# 10-USB-Prog.net
KiCad netlist of a schematic drawn in Altium Designer
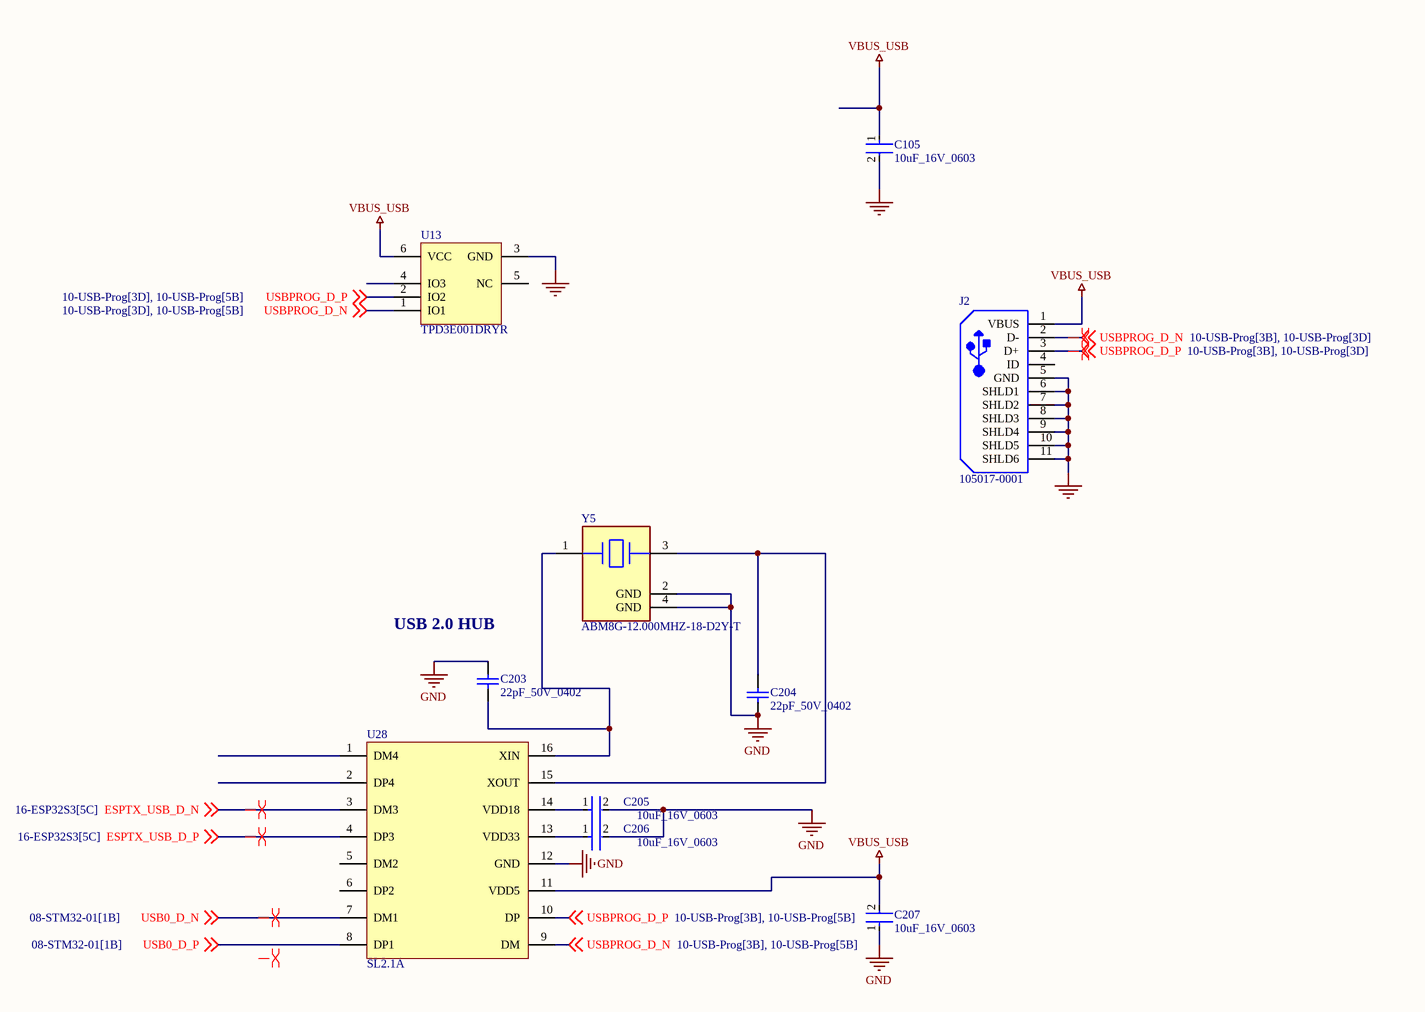
[diagram p0: 10-USB-Prog.SchDoc]

(export (version "E")
  (design (tool "Eeschema 10.0.6"))
  (components
    (comp (ref "C105")
      (value "10uF_16V_0603")
      (footprint "FP-0603-L_1_6_0_2-W_0_8_0-MFG")
      (description "Multilayer Ceramic Capacitor 10uF 16V X5R 20% SMD 0603 T/R")
      (fields (field (name "TOLERANCE") "20%"))
      (libsource (lib "Altium Content Vault") (part "b4654b650e69147ec39a6b967a45e02"))
    )
    (comp (ref "C203")
      (value "22pF_50V_0402")
      (footprint "CAPC1005X55X25ML05T05")
      (description "Chip Capacitor, 22 pF, +/- 5%, 50 V, -55 to 125 degC, 0402 (1005 Metric), RoHS, Tape and Reel")
      (fields (field (name "MANUFACTURER") "Yageo") (field (name "TOLERANCE") "5%"))
      (libsource (lib "Altium Content Vault") (part "CAP-NP-2"))
    )
    (comp (ref "C204")
      (value "22pF_50V_0402")
      (footprint "CAPC1005X55X25ML05T05")
      (description "Chip Capacitor, 22 pF, +/- 5%, 50 V, -55 to 125 degC, 0402 (1005 Metric), RoHS, Tape and Reel")
      (fields (field (name "MANUFACTURER") "Yageo") (field (name "TOLERANCE") "5%"))
      (libsource (lib "Altium Content Vault") (part "CAP-NP-2"))
    )
    (comp (ref "C205")
      (value "10uF_16V_0603")
      (footprint "FP-0603-L_1_6_0_2-W_0_8_0-MFG")
      (description "Multilayer Ceramic Capacitor 10uF 16V X5R 20% SMD 0603 T/R")
      (fields (field (name "TOLERANCE") "20%"))
      (libsource (lib "Altium Content Vault") (part "b4654b650e69147ec39a6b967a45e02"))
    )
    (comp (ref "C206")
      (value "10uF_16V_0603")
      (footprint "FP-0603-L_1_6_0_2-W_0_8_0-MFG")
      (description "Multilayer Ceramic Capacitor 10uF 16V X5R 20% SMD 0603 T/R")
      (fields (field (name "TOLERANCE") "20%"))
      (libsource (lib "Altium Content Vault") (part "b4654b650e69147ec39a6b967a45e02"))
    )
    (comp (ref "C207")
      (value "10uF_16V_0603")
      (footprint "FP-0603-L_1_6_0_2-W_0_8_0-MFG")
      (description "Multilayer Ceramic Capacitor 10uF 16V X5R 20% SMD 0603 T/R")
      (fields (field (name "TOLERANCE") "20%"))
      (libsource (lib "Altium Content Vault") (part "b4654b650e69147ec39a6b967a45e02"))
    )
    (comp (ref "J2")
      (value "105017-0001")
      (footprint "USB-MICRO-B_V")
      (fields (field (name "MANUFACTURER") "Molex"))
      (libsource (lib "Altium Content Vault") (part "USB-5-6SHLD"))
    )
    (comp (ref "U13")
      (value "TPD3E001DRYR")
      (footprint "DRY0006A")
      (fields (field (name "MANUFACTURER") "Texas Instruments"))
      (libsource (lib "Altium Content Vault") (part "TI-TPD3E001-SON_DRY-6"))
    )
    (comp (ref "U28")
      (value "SL2.1A")
      (footprint "IC_SL2.1A")
      (description "USB 2.0 HIGH SPEED 4-PORT HUB CONTROLLER")
      (fields (field (name "MF") "CoreChips ShenZhen CO.,Ltd"))
      (libsource (lib "LotusSound") (part "IC_SL2.1A"))
    )
    (comp (ref "Y5")
      (value "ABM8G-12.000MHZ-18-D2Y-T")
      (footprint "FP-ABM8G-MFG")
      (description "Crystal 12MHz ±20ppm (Tol) ±30ppm (Stability) 18pF FUND 120Ω 4-Pin SMD T/R")
      (fields (field (name "TOLERANCE") "20ppm"))
      (libsource (lib "Altium Content Vault") (part "48e526d86b7f2615d98721063c72f49"))
    )
  )
  (nets
    (net (code "1") (name "ESPTX_USB_D_N") (class "Default")
      (node (ref "U28") (pin "3") (pinfunction "DM3_3") (pintype "passive"))
    )
    (net (code "2") (name "ESPTX_USB_D_P") (class "Default")
      (node (ref "U28") (pin "4") (pinfunction "DP3_4") (pintype "passive"))
    )
    (net (code "3") (name "GND") (class "Default")
      (node (ref "C105") (pin "2") (pinfunction "2_2") (pintype "passive"))
      (node (ref "C203") (pin "2") (pinfunction "2_2") (pintype "passive"))
      (node (ref "C204") (pin "1") (pinfunction "1_1") (pintype "passive"))
      (node (ref "C205") (pin "2") (pinfunction "2_2") (pintype "passive"))
      (node (ref "C206") (pin "2") (pinfunction "2_2") (pintype "passive"))
      (node (ref "C207") (pin "1") (pinfunction "1_1") (pintype "passive"))
      (node (ref "J2") (pin "10") (pinfunction "SHLD5_10") (pintype "passive"))
      (node (ref "J2") (pin "11") (pinfunction "SHLD6_11") (pintype "passive"))
      (node (ref "J2") (pin "5") (pinfunction "GND_5") (pintype "passive"))
      (node (ref "J2") (pin "6") (pinfunction "SHLD1_6") (pintype "passive"))
      (node (ref "J2") (pin "7") (pinfunction "SHLD2_7") (pintype "passive"))
      (node (ref "J2") (pin "8") (pinfunction "SHLD3_8") (pintype "passive"))
      (node (ref "J2") (pin "9") (pinfunction "SHLD4_9") (pintype "passive"))
      (node (ref "U13") (pin "3") (pinfunction "GND_3") (pintype "power_in"))
      (node (ref "U28") (pin "12") (pinfunction "GND_12") (pintype "passive"))
      (node (ref "Y5") (pin "2") (pinfunction "GND_2") (pintype "power_in"))
      (node (ref "Y5") (pin "4") (pinfunction "GND_4") (pintype "power_in"))
    )
    (net (code "4") (name "Net-(U28-VDD18)") (class "Default")
      (node (ref "C205") (pin "1") (pinfunction "1_1") (pintype "passive"))
      (node (ref "U28") (pin "14") (pinfunction "VDD18_14") (pintype "passive"))
    )
    (net (code "5") (name "Net-(U28-VDD33)") (class "Default")
      (node (ref "C206") (pin "1") (pinfunction "1_1") (pintype "passive"))
      (node (ref "U28") (pin "13") (pinfunction "VDD33_13") (pintype "passive"))
    )
    (net (code "6") (name "Net-(U28-XIN)") (class "Default")
      (node (ref "C203") (pin "1") (pinfunction "1_1") (pintype "passive"))
      (node (ref "U28") (pin "16") (pinfunction "XIN_16") (pintype "passive"))
      (node (ref "Y5") (pin "1") (pinfunction "1_1") (pintype "passive"))
    )
    (net (code "7") (name "Net-(U28-XOUT)") (class "Default")
      (node (ref "C204") (pin "2") (pinfunction "2_2") (pintype "passive"))
      (node (ref "U28") (pin "15") (pinfunction "XOUT_15") (pintype "passive"))
      (node (ref "Y5") (pin "3") (pinfunction "3_3") (pintype "passive"))
    )
    (net (code "8") (name "USB0_D_N") (class "Default")
      (node (ref "U28") (pin "7") (pinfunction "DM1_7") (pintype "passive"))
    )
    (net (code "9") (name "USB0_D_P") (class "Default")
      (node (ref "U28") (pin "8") (pinfunction "DP1_8") (pintype "passive"))
    )
    (net (code "10") (name "USBPROG_D_N") (class "Default")
      (node (ref "J2") (pin "2") (pinfunction "D-_2") (pintype "passive"))
      (node (ref "U13") (pin "1") (pinfunction "IO1_1") (pintype "passive"))
      (node (ref "U28") (pin "9") (pinfunction "DM_9") (pintype "passive"))
    )
    (net (code "11") (name "USBPROG_D_P") (class "Default")
      (node (ref "J2") (pin "3") (pinfunction "D+_3") (pintype "passive"))
      (node (ref "U13") (pin "2") (pinfunction "IO2_2") (pintype "passive"))
      (node (ref "U28") (pin "10") (pinfunction "DP_10") (pintype "passive"))
    )
    (net (code "12") (name "VBUS_USB") (class "Default")
      (node (ref "C105") (pin "1") (pinfunction "1_1") (pintype "passive"))
      (node (ref "C207") (pin "2") (pinfunction "2_2") (pintype "passive"))
      (node (ref "J2") (pin "1") (pinfunction "VBUS_1") (pintype "passive"))
      (node (ref "U13") (pin "6") (pinfunction "VCC_6") (pintype "power_in"))
      (node (ref "U28") (pin "11") (pinfunction "VDD5_11") (pintype "passive"))
    )
    (net (code "13") (name "unconnected-(J2-ID-Pad4)") (class "Default")
      (node (ref "J2") (pin "4") (pinfunction "ID_4") (pintype "passive"))
    )
    (net (code "14") (name "unconnected-(U13-IO3-Pad4)") (class "Default")
      (node (ref "U13") (pin "4") (pinfunction "IO3_4") (pintype "passive"))
    )
    (net (code "15") (name "unconnected-(U13-NC-Pad5)") (class "Default")
      (node (ref "U13") (pin "5") (pinfunction "NC_5") (pintype "passive"))
    )
    (net (code "16") (name "unconnected-(U28-DM2-Pad5)") (class "Default")
      (node (ref "U28") (pin "5") (pinfunction "DM2_5") (pintype "passive"))
    )
    (net (code "17") (name "unconnected-(U28-DM4-Pad1)") (class "Default")
      (node (ref "U28") (pin "1") (pinfunction "DM4_1") (pintype "passive"))
    )
    (net (code "18") (name "unconnected-(U28-DP2-Pad6)") (class "Default")
      (node (ref "U28") (pin "6") (pinfunction "DP2_6") (pintype "passive"))
    )
    (net (code "19") (name "unconnected-(U28-DP4-Pad2)") (class "Default")
      (node (ref "U28") (pin "2") (pinfunction "DP4_2") (pintype "passive"))
    )
  )
)
